# 4x4_Keypad.net
KiCad netlist of a schematic drawn in EasyEDA
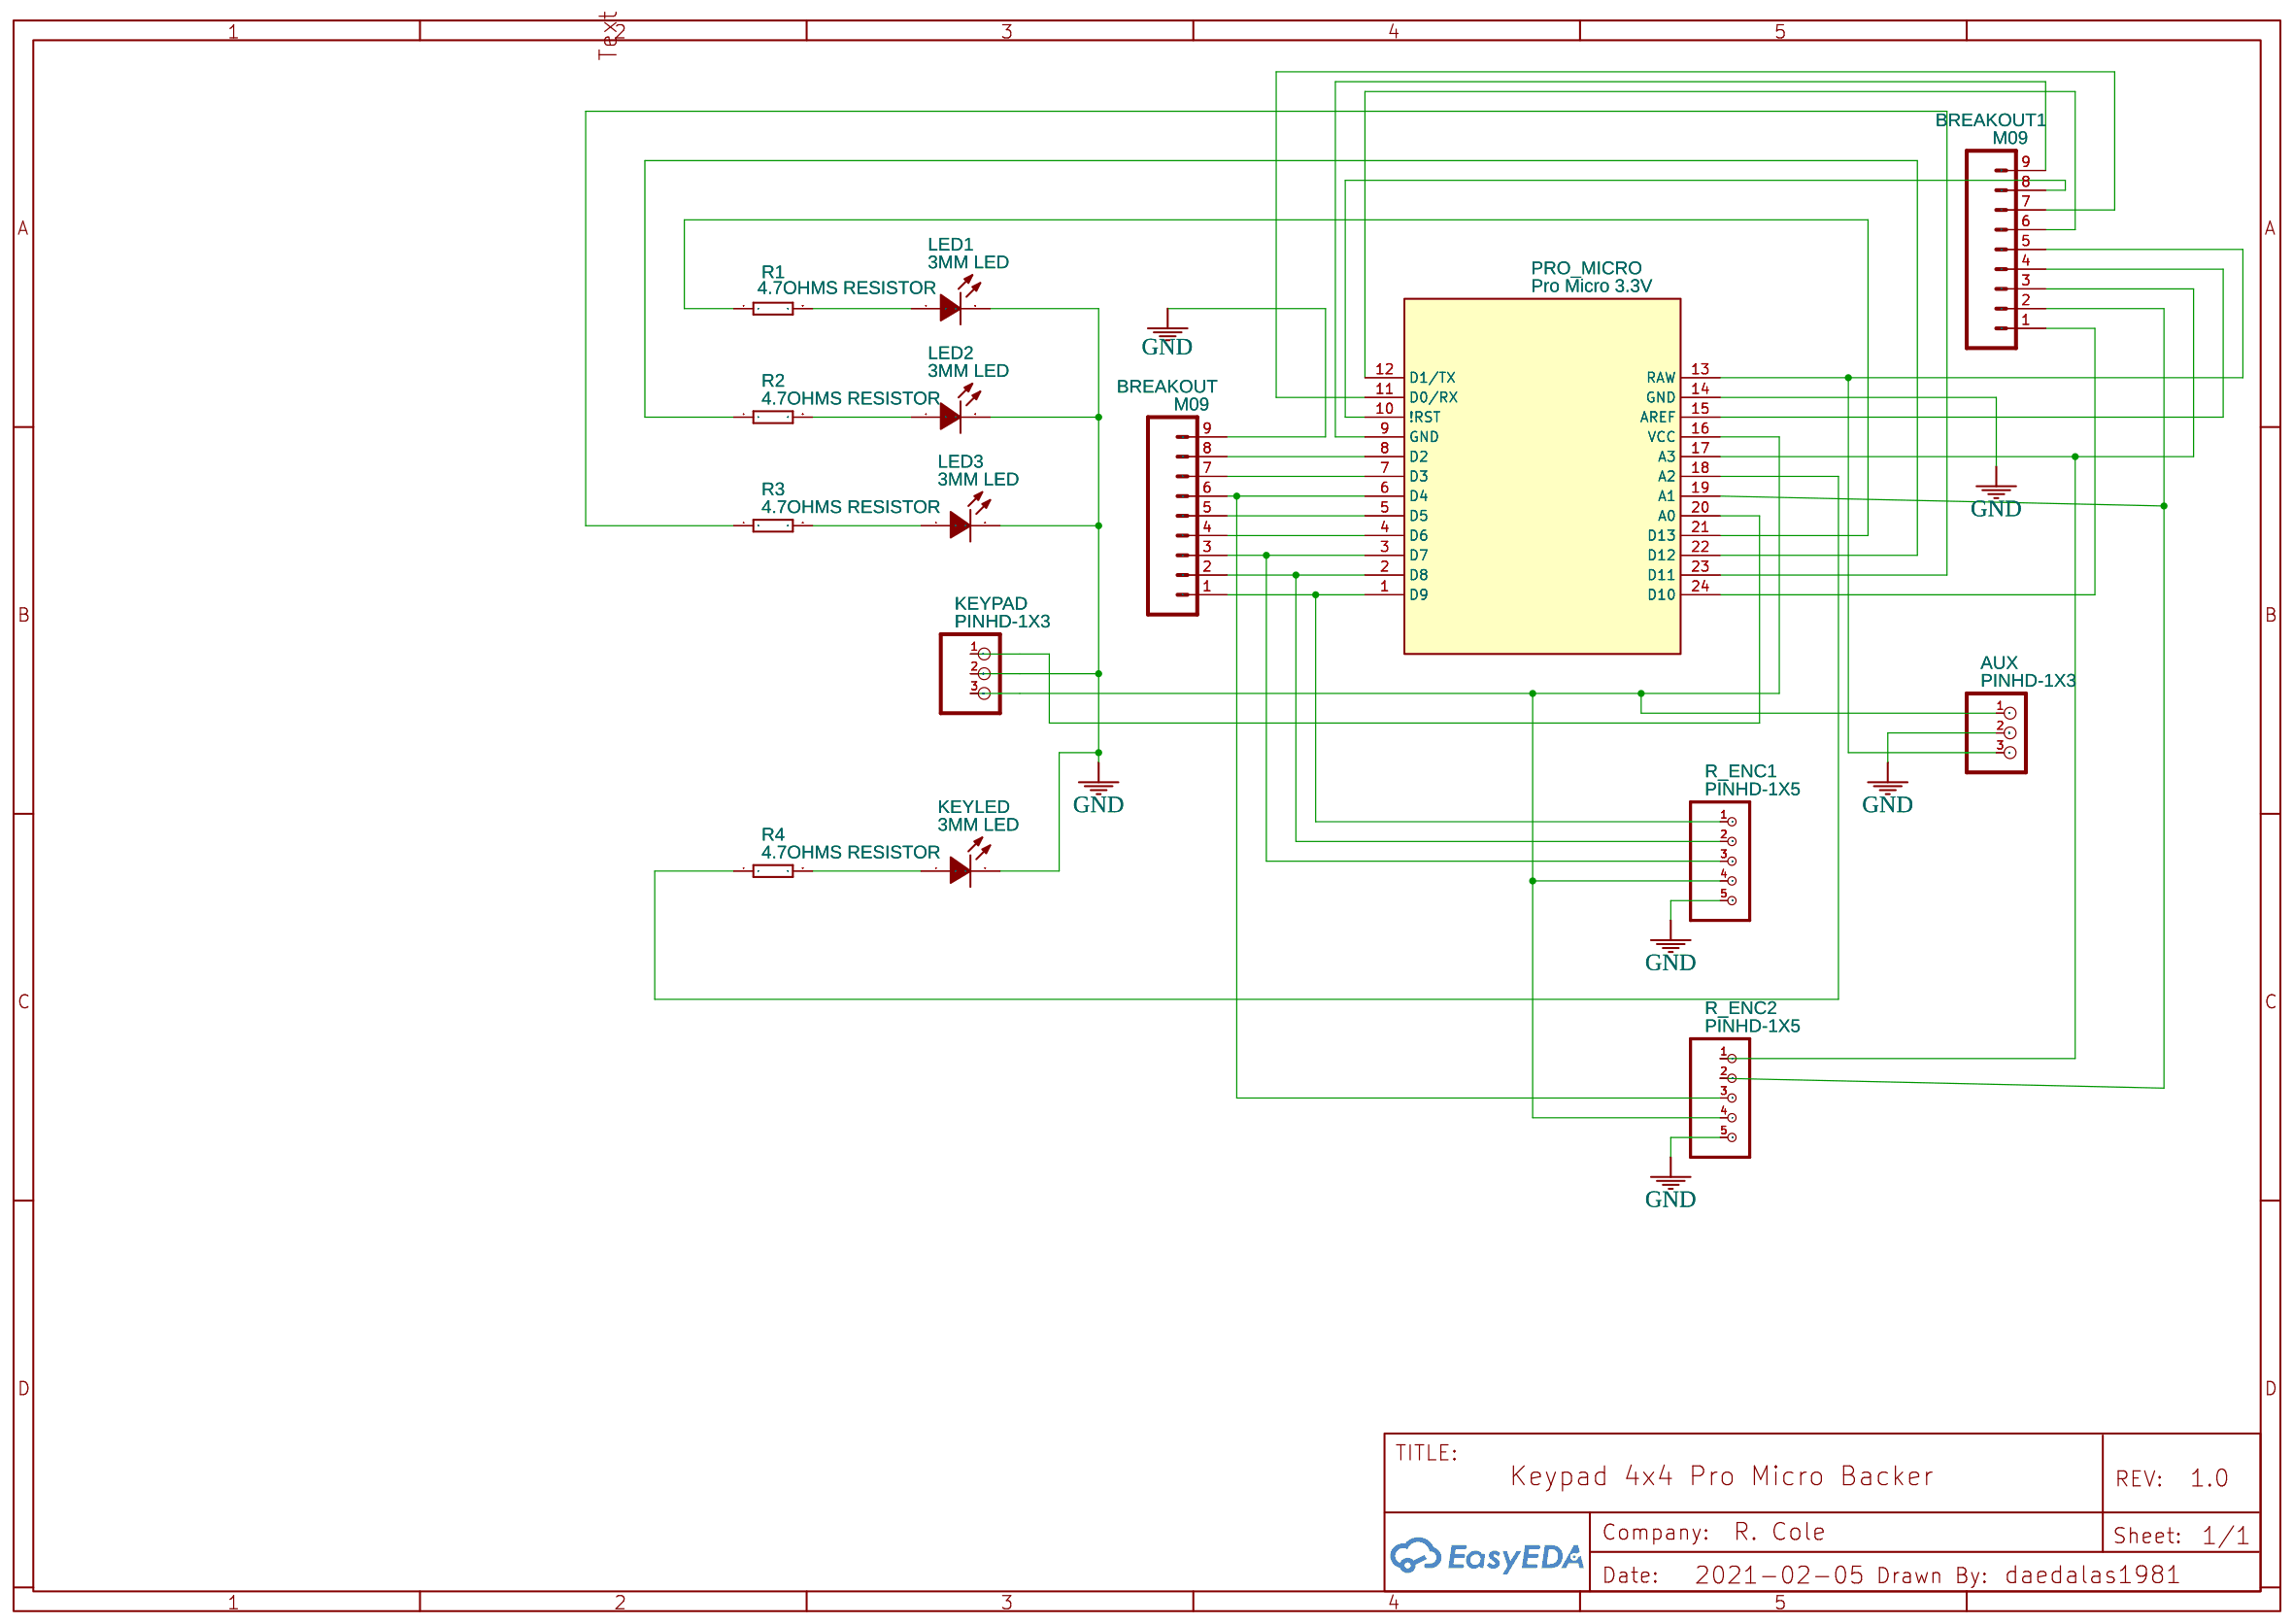
[diagram p0: schematic sheet]

(export (version "E")
  (design (tool "Eeschema 10.0.6"))
  (components
    (comp (ref "AUX") (value "PINHD-1X3") (libsource (lib "") (part "PINHD-1X3")))
    (comp (ref "BREAKOUT") (value "M09") (libsource (lib "") (part "M09")))
    (comp (ref "BREAKOUT1") (value "M09") (libsource (lib "") (part "M09")))
    (comp (ref "KEYLED")
      (value "3MM LED")
      (fields (field (name "BOM_Manufacturer Part") "3ARB9HCB") (field (name "BOM_Supplier Part") "C42016"))
      (libsource (lib "") (part "3MM LED_1"))
    )
    (comp (ref "KEYPAD") (value "PINHD-1X3") (libsource (lib "") (part "PINHD-1X3_1")))
    (comp (ref "LED1")
      (value "3MM LED")
      (fields (field (name "BOM_Manufacturer Part") "3ARB9HCB") (field (name "BOM_Supplier Part") "C42016"))
      (libsource (lib "") (part "3MM LED"))
    )
    (comp (ref "LED2")
      (value "3MM LED")
      (fields (field (name "BOM_Manufacturer Part") "3ARB9HCB") (field (name "BOM_Supplier Part") "C42016"))
      (libsource (lib "") (part "3MM LED"))
    )
    (comp (ref "LED3")
      (value "3MM LED")
      (fields (field (name "BOM_Manufacturer Part") "3ARB9HCB") (field (name "BOM_Supplier Part") "C42016"))
      (libsource (lib "") (part "3MM LED"))
    )
    (comp (ref "PRO_MICRO")
      (value "Pro Micro 3.3V")
      (fields (field (name "BOM_Supplier Part") "12587"))
      (libsource (lib "") (part "Pro Micro 3.3V"))
    )
    (comp (ref "R1") (value "4.7OHMS RESISTOR") (libsource (lib "") (part "RESISTOR")))
    (comp (ref "R2") (value "4.7OHMS RESISTOR") (libsource (lib "") (part "RESISTOR")))
    (comp (ref "R3") (value "4.7OHMS RESISTOR") (libsource (lib "") (part "RESISTOR")))
    (comp (ref "R4") (value "4.7OHMS RESISTOR") (libsource (lib "") (part "RESISTOR")))
    (comp (ref "R_ENC1") (value "PINHD-1X5") (libsource (lib "") (part "PINHD-1X5")))
    (comp (ref "R_ENC2") (value "PINHD-1X5") (libsource (lib "") (part "PINHD-1X5")))
  )
  (nets
    (net (code "1") (name "GND") (class "Default")
      (node (ref "AUX") (pin "2") (pinfunction "GND_2") (pintype "unspecified"))
      (node (ref "BREAKOUT") (pin "9") (pinfunction "9_9") (pintype "unspecified"))
      (node (ref "KEYLED") (pin "2") (pinfunction "K_2") (pintype "unspecified"))
      (node (ref "KEYPAD") (pin "2") (pinfunction "GND_2") (pintype "unspecified"))
      (node (ref "LED1") (pin "2") (pinfunction "K_2") (pintype "unspecified"))
      (node (ref "LED2") (pin "2") (pinfunction "K_2") (pintype "unspecified"))
      (node (ref "LED3") (pin "2") (pinfunction "K_2") (pintype "unspecified"))
      (node (ref "PRO_MICRO") (pin "14") (pinfunction "GND_14") (pintype "unspecified"))
      (node (ref "R_ENC1") (pin "5") (pinfunction "5_5") (pintype "bidirectional"))
      (node (ref "R_ENC2") (pin "5") (pinfunction "5_5") (pintype "bidirectional"))
    )
    (net (code "2") (name "Net-(AUX-RAW)") (class "Default")
      (node (ref "AUX") (pin "3") (pinfunction "RAW_3") (pintype "unspecified"))
      (node (ref "BREAKOUT1") (pin "5") (pinfunction "5_5") (pintype "unspecified"))
      (node (ref "PRO_MICRO") (pin "13") (pinfunction "RAW_13") (pintype "unspecified"))
    )
    (net (code "3") (name "Net-(AUX-VCC)") (class "Default")
      (node (ref "AUX") (pin "1") (pinfunction "VCC_1") (pintype "unspecified"))
      (node (ref "KEYPAD") (pin "3") (pinfunction "VCC_3") (pintype "unspecified"))
      (node (ref "PRO_MICRO") (pin "16") (pinfunction "VCC_16") (pintype "unspecified"))
      (node (ref "R_ENC1") (pin "4") (pinfunction "4_4") (pintype "bidirectional"))
      (node (ref "R_ENC2") (pin "4") (pinfunction "4_4") (pintype "bidirectional"))
    )
    (net (code "4") (name "Net-(BREAKOUT1-Pad9)") (class "Default")
      (node (ref "BREAKOUT1") (pin "9") (pinfunction "9_9") (pintype "unspecified"))
      (node (ref "PRO_MICRO") (pin "9") (pinfunction "GND_9") (pintype "unspecified"))
    )
    (net (code "5") (name "Net-(KEYLED-A)") (class "Default")
      (node (ref "KEYLED") (pin "1") (pinfunction "A_1") (pintype "unspecified"))
      (node (ref "R4") (pin "2") (pinfunction "2_2") (pintype "unspecified"))
    )
    (net (code "6") (name "Net-(KEYPAD-AIN)") (class "Default")
      (node (ref "KEYPAD") (pin "1") (pinfunction "AIN_1") (pintype "unspecified"))
      (node (ref "PRO_MICRO") (pin "20") (pinfunction "A0_20") (pintype "unspecified"))
    )
    (net (code "7") (name "Net-(LED1-A)") (class "Default")
      (node (ref "LED1") (pin "1") (pinfunction "A_1") (pintype "unspecified"))
      (node (ref "R1") (pin "2") (pinfunction "2_2") (pintype "unspecified"))
    )
    (net (code "8") (name "Net-(LED2-A)") (class "Default")
      (node (ref "LED2") (pin "1") (pinfunction "A_1") (pintype "unspecified"))
      (node (ref "R2") (pin "2") (pinfunction "2_2") (pintype "unspecified"))
    )
    (net (code "9") (name "Net-(LED3-A)") (class "Default")
      (node (ref "LED3") (pin "1") (pinfunction "A_1") (pintype "unspecified"))
      (node (ref "R3") (pin "2") (pinfunction "2_2") (pintype "unspecified"))
    )
    (net (code "10") (name "Net-(PRO_MICRO-!RST)") (class "Default")
      (node (ref "BREAKOUT1") (pin "8") (pinfunction "8_8") (pintype "unspecified"))
      (node (ref "PRO_MICRO") (pin "10") (pinfunction "!RST_10") (pintype "unspecified"))
    )
    (net (code "11") (name "Net-(PRO_MICRO-A1)") (class "Default")
      (node (ref "BREAKOUT1") (pin "2") (pinfunction "2_2") (pintype "unspecified"))
      (node (ref "PRO_MICRO") (pin "19") (pinfunction "A1_19") (pintype "unspecified"))
      (node (ref "R_ENC2") (pin "2") (pinfunction "2_2") (pintype "bidirectional"))
    )
    (net (code "12") (name "Net-(PRO_MICRO-A2)") (class "Default")
      (node (ref "PRO_MICRO") (pin "18") (pinfunction "A2_18") (pintype "unspecified"))
      (node (ref "R4") (pin "1") (pinfunction "1_1") (pintype "unspecified"))
    )
    (net (code "13") (name "Net-(PRO_MICRO-A3)") (class "Default")
      (node (ref "BREAKOUT1") (pin "3") (pinfunction "3_3") (pintype "unspecified"))
      (node (ref "PRO_MICRO") (pin "17") (pinfunction "A3_17") (pintype "unspecified"))
      (node (ref "R_ENC2") (pin "1") (pinfunction "1_1") (pintype "bidirectional"))
    )
    (net (code "14") (name "Net-(PRO_MICRO-AREF)") (class "Default")
      (node (ref "BREAKOUT1") (pin "4") (pinfunction "4_4") (pintype "unspecified"))
      (node (ref "PRO_MICRO") (pin "15") (pinfunction "AREF_15") (pintype "unspecified"))
    )
    (net (code "15") (name "Net-(PRO_MICRO-D0{slash}RX)") (class "Default")
      (node (ref "BREAKOUT1") (pin "7") (pinfunction "7_7") (pintype "unspecified"))
      (node (ref "PRO_MICRO") (pin "11") (pinfunction "D0/RX_11") (pintype "unspecified"))
    )
    (net (code "16") (name "Net-(PRO_MICRO-D1{slash}TX)") (class "Default")
      (node (ref "BREAKOUT1") (pin "6") (pinfunction "6_6") (pintype "unspecified"))
      (node (ref "PRO_MICRO") (pin "12") (pinfunction "D1/TX_12") (pintype "unspecified"))
    )
    (net (code "17") (name "Net-(PRO_MICRO-D2)") (class "Default")
      (node (ref "BREAKOUT") (pin "8") (pinfunction "8_8") (pintype "unspecified"))
      (node (ref "PRO_MICRO") (pin "8") (pinfunction "D2_8") (pintype "unspecified"))
    )
    (net (code "18") (name "Net-(PRO_MICRO-D3)") (class "Default")
      (node (ref "BREAKOUT") (pin "7") (pinfunction "7_7") (pintype "unspecified"))
      (node (ref "PRO_MICRO") (pin "7") (pinfunction "D3_7") (pintype "unspecified"))
    )
    (net (code "19") (name "Net-(PRO_MICRO-D4)") (class "Default")
      (node (ref "BREAKOUT") (pin "6") (pinfunction "6_6") (pintype "unspecified"))
      (node (ref "PRO_MICRO") (pin "6") (pinfunction "D4_6") (pintype "unspecified"))
      (node (ref "R_ENC2") (pin "3") (pinfunction "3_3") (pintype "bidirectional"))
    )
    (net (code "20") (name "Net-(PRO_MICRO-D5)") (class "Default")
      (node (ref "BREAKOUT") (pin "5") (pinfunction "5_5") (pintype "unspecified"))
      (node (ref "PRO_MICRO") (pin "5") (pinfunction "D5_5") (pintype "unspecified"))
    )
    (net (code "21") (name "Net-(PRO_MICRO-D6)") (class "Default")
      (node (ref "BREAKOUT") (pin "4") (pinfunction "4_4") (pintype "unspecified"))
      (node (ref "PRO_MICRO") (pin "4") (pinfunction "D6_4") (pintype "unspecified"))
    )
    (net (code "22") (name "Net-(PRO_MICRO-D7)") (class "Default")
      (node (ref "BREAKOUT") (pin "3") (pinfunction "3_3") (pintype "unspecified"))
      (node (ref "PRO_MICRO") (pin "3") (pinfunction "D7_3") (pintype "unspecified"))
      (node (ref "R_ENC1") (pin "3") (pinfunction "3_3") (pintype "bidirectional"))
    )
    (net (code "23") (name "Net-(PRO_MICRO-D8)") (class "Default")
      (node (ref "BREAKOUT") (pin "2") (pinfunction "2_2") (pintype "unspecified"))
      (node (ref "PRO_MICRO") (pin "2") (pinfunction "D8_2") (pintype "unspecified"))
      (node (ref "R_ENC1") (pin "2") (pinfunction "2_2") (pintype "bidirectional"))
    )
    (net (code "24") (name "Net-(PRO_MICRO-D9)") (class "Default")
      (node (ref "BREAKOUT") (pin "1") (pinfunction "1_1") (pintype "unspecified"))
      (node (ref "PRO_MICRO") (pin "1") (pinfunction "D9_1") (pintype "unspecified"))
      (node (ref "R_ENC1") (pin "1") (pinfunction "1_1") (pintype "bidirectional"))
    )
    (net (code "25") (name "Net-(PRO_MICRO-D10)") (class "Default")
      (node (ref "BREAKOUT1") (pin "1") (pinfunction "1_1") (pintype "unspecified"))
      (node (ref "PRO_MICRO") (pin "24") (pinfunction "D10_24") (pintype "unspecified"))
    )
    (net (code "26") (name "Net-(PRO_MICRO-D11)") (class "Default")
      (node (ref "PRO_MICRO") (pin "23") (pinfunction "D11_23") (pintype "unspecified"))
      (node (ref "R3") (pin "1") (pinfunction "1_1") (pintype "unspecified"))
    )
    (net (code "27") (name "Net-(PRO_MICRO-D12)") (class "Default")
      (node (ref "PRO_MICRO") (pin "22") (pinfunction "D12_22") (pintype "unspecified"))
      (node (ref "R2") (pin "1") (pinfunction "1_1") (pintype "unspecified"))
    )
    (net (code "28") (name "Net-(PRO_MICRO-D13)") (class "Default")
      (node (ref "PRO_MICRO") (pin "21") (pinfunction "D13_21") (pintype "unspecified"))
      (node (ref "R1") (pin "1") (pinfunction "1_1") (pintype "unspecified"))
    )
  )
)
